# VrefSch.net
KiCad netlist of a schematic drawn in Altium Designer
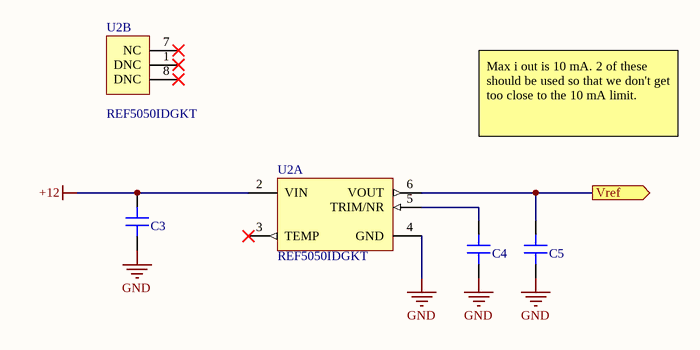
[diagram p0: VrefSch.SchDoc]

(export (version "E")
  (design (tool "Eeschema 10.0.6"))
  (components
    (comp (ref "C3")
      (value "1uF")
      (footprint "CAP 0805/2012")
      (description "CAP CER 1UF 25V X7R 0805")
      (fields (field (name "PART NUMBER") "C0805C105J3RACTU") (field (name "MANUFACTURER") "Kemet"))
      (libsource (lib "Celestial Library Database") (part "Capacitor"))
    )
    (comp (ref "C4")
      (value "1uF")
      (footprint "CAP 0805/2012")
      (description "CAP CER 1UF 25V X7R 0805")
      (fields (field (name "PART NUMBER") "C0805C105J3RACTU") (field (name "MANUFACTURER") "Kemet"))
      (libsource (lib "Celestial Library Database") (part "Capacitor"))
    )
    (comp (ref "C5")
      (value "1uF")
      (footprint "CAP 0805/2012")
      (description "CAP CER 1UF 25V X7R 0805")
      (fields (field (name "PART NUMBER") "C0805C105J3RACTU") (field (name "MANUFACTURER") "Kemet"))
      (libsource (lib "Celestial Library Database") (part "Capacitor"))
    )
    (comp (ref "U2")
      (value "REF5050IDGKT")
      (footprint "DGK0008A_N")
      (fields (field (name "MANUFACTURER") "Texas Instruments"))
      (libsource (lib "Altium Content Vault") (part "TI-REF5050DGK8"))
    )
  )
  (nets
    (net (code "1") (name "+12") (class "Default")
      (node (ref "C3") (pin "2") (pinfunction "2_2") (pintype "passive"))
      (node (ref "U2") (pin "2") (pinfunction "VIN_2") (pintype "power_in"))
    )
    (net (code "2") (name "/Vref") (class "Default")
      (node (ref "C5") (pin "2") (pinfunction "2_2") (pintype "passive"))
      (node (ref "U2") (pin "6") (pinfunction "VOUT_6") (pintype "output"))
    )
    (net (code "3") (name "GND") (class "Default")
      (node (ref "C3") (pin "1") (pinfunction "1_1") (pintype "passive"))
      (node (ref "C4") (pin "1") (pinfunction "1_1") (pintype "passive"))
      (node (ref "C5") (pin "1") (pinfunction "1_1") (pintype "passive"))
      (node (ref "U2") (pin "4") (pinfunction "GND_4") (pintype "power_in"))
    )
    (net (code "4") (name "Net-(U2A-TRIM{slash}NR)") (class "Default")
      (node (ref "C4") (pin "2") (pinfunction "2_2") (pintype "passive"))
      (node (ref "U2") (pin "5") (pinfunction "TRIM/NR_5") (pintype "input"))
    )
    (net (code "5") (name "unconnected-(U2A-TEMP-Pad3)") (class "Default")
      (node (ref "U2") (pin "3") (pinfunction "TEMP_3") (pintype "output+no_connect"))
    )
    (net (code "6") (name "unconnected-(U2B-DNC-Pad1)") (class "Default")
      (node (ref "U2") (pin "1") (pinfunction "DNC_1") (pintype "passive+no_connect"))
    )
    (net (code "7") (name "unconnected-(U2B-DNC-Pad8)") (class "Default")
      (node (ref "U2") (pin "8") (pinfunction "DNC_8") (pintype "passive+no_connect"))
    )
    (net (code "8") (name "unconnected-(U2B-NC-Pad7)") (class "Default")
      (node (ref "U2") (pin "7") (pinfunction "NC_7") (pintype "passive+no_connect"))
    )
  )
)
